# Affective_Shield.net
KiCad netlist of a schematic drawn in EAGLE
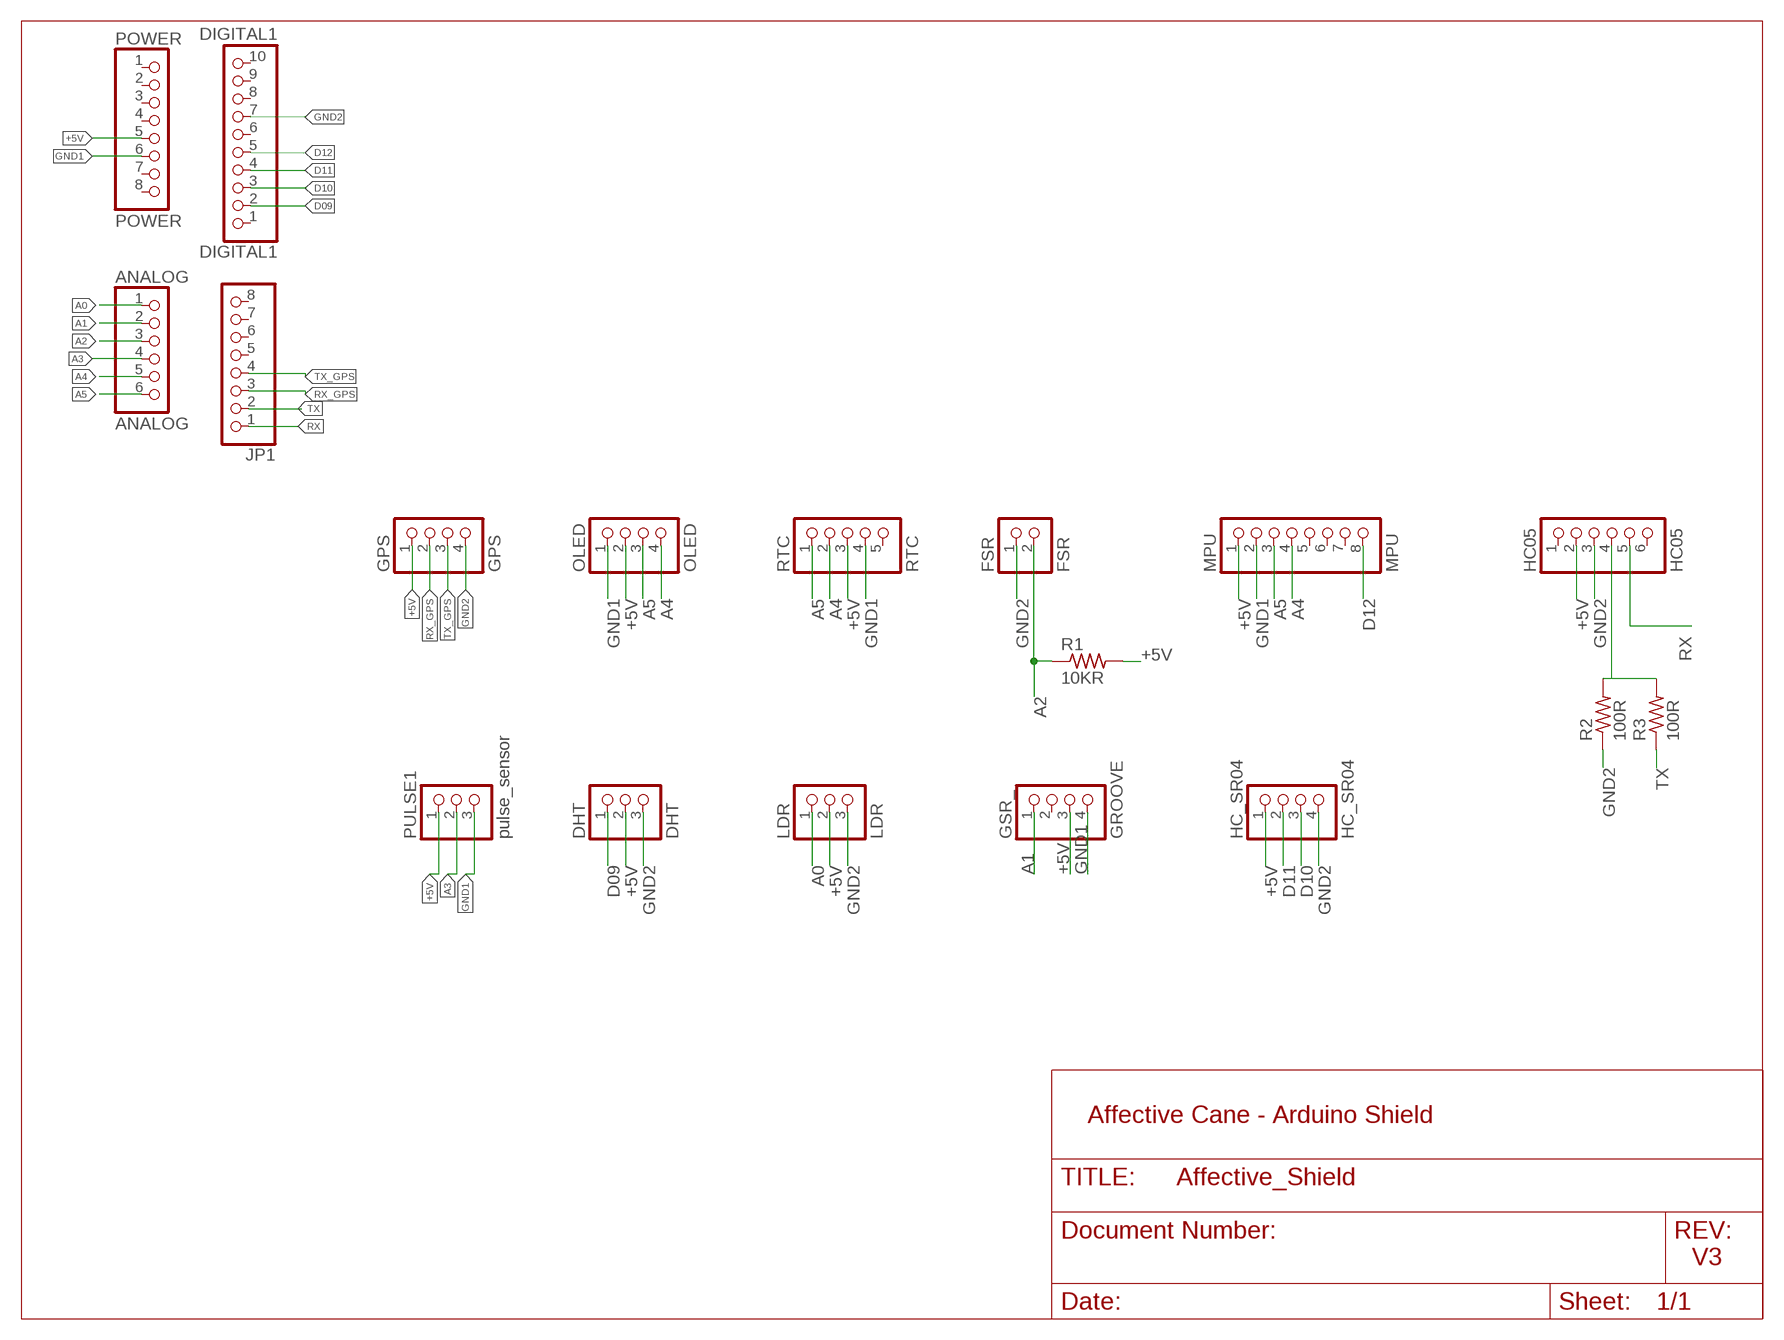
[diagram p0: schematic, sheet 1]

(export (version "E")
  (design (tool "Eeschema 10.0.6"))
  (components
    (comp (ref "ANALOG")
      (value "ANALOG")
      (footprint "eagle-import:1X06")
      (libsource (lib "eagle-import") (part "PINHD-1X6"))
    )
    (comp (ref "DHT")
      (value "DHT")
      (footprint "eagle-import:1X03")
      (libsource (lib "eagle-import") (part "PINHD-1X3"))
    )
    (comp (ref "DIGITAL1")
      (value "DIGITAL1")
      (footprint "eagle-import:1X10")
      (libsource (lib "eagle-import") (part "PINHD-1X10"))
    )
    (comp (ref "FSR")
      (value "FSR")
      (footprint "eagle-import:1X02")
      (libsource (lib "eagle-import") (part "PINHD-1X2"))
    )
    (comp (ref "GPS")
      (value "GPS")
      (footprint "eagle-import:1X04")
      (libsource (lib "eagle-import") (part "PINHD-1X4"))
    )
    (comp (ref "GSR_")
      (value "GROOVE")
      (footprint "eagle-import:1X04")
      (libsource (lib "eagle-import") (part "PINHD-1X4"))
    )
    (comp (ref "HC05")
      (value "HC05")
      (footprint "eagle-import:1X06")
      (libsource (lib "eagle-import") (part "PINHD-1X6"))
    )
    (comp (ref "HC_SR04")
      (value "HC_SR04")
      (footprint "eagle-import:1X04")
      (libsource (lib "eagle-import") (part "PINHD-1X4"))
    )
    (comp (ref "JP1")
      (value "PINHD-1X8")
      (footprint "eagle-import:1X08")
      (libsource (lib "eagle-import") (part "PINHD-1X8"))
    )
    (comp (ref "LDR")
      (value "LDR")
      (footprint "eagle-import:1X03")
      (libsource (lib "eagle-import") (part "PINHD-1X3"))
    )
    (comp (ref "MPU")
      (value "MPU")
      (footprint "eagle-import:1X08")
      (libsource (lib "eagle-import") (part "PINHD-1X8"))
    )
    (comp (ref "OLED")
      (value "OLED")
      (footprint "eagle-import:1X04")
      (libsource (lib "eagle-import") (part "PINHD-1X4"))
    )
    (comp (ref "POWER")
      (value "POWER")
      (footprint "eagle-import:1X08")
      (libsource (lib "eagle-import") (part "PINHD-1X8"))
    )
    (comp (ref "PULSE1")
      (value "pulse_sensor")
      (footprint "eagle-import:1X03")
      (libsource (lib "eagle-import") (part "PINHD-1X3"))
    )
    (comp (ref "R1")
      (value "10KR")
      (footprint "eagle-import:0204_7")
      (libsource (lib "eagle-import") (part "R-US_0204/7"))
    )
    (comp (ref "R2")
      (value "100R")
      (footprint "eagle-import:0204_7")
      (libsource (lib "eagle-import") (part "R-US_0204/7"))
    )
    (comp (ref "R3")
      (value "100R")
      (footprint "eagle-import:0204_7")
      (libsource (lib "eagle-import") (part "R-US_0204/7"))
    )
    (comp (ref "RTC")
      (value "RTC")
      (footprint "eagle-import:1X05")
      (libsource (lib "eagle-import") (part "PINHD-1X5"))
    )
  )
  (nets
    (net (code "1") (name "+5V") (class "Default")
      (node (ref "DHT") (pin "2") (pinfunction "2_2") (pintype "passive"))
      (node (ref "GPS") (pin "1") (pinfunction "1_1") (pintype "passive"))
      (node (ref "GSR_") (pin "3") (pinfunction "3_3") (pintype "passive"))
      (node (ref "HC05") (pin "2") (pinfunction "2_2") (pintype "passive"))
      (node (ref "HC_SR04") (pin "1") (pinfunction "1_1") (pintype "passive"))
      (node (ref "LDR") (pin "2") (pinfunction "2_2") (pintype "passive"))
      (node (ref "MPU") (pin "1") (pinfunction "1_1") (pintype "passive"))
      (node (ref "OLED") (pin "2") (pinfunction "2_2") (pintype "passive"))
      (node (ref "POWER") (pin "5") (pinfunction "5_5") (pintype "passive"))
      (node (ref "PULSE1") (pin "1") (pinfunction "1_1") (pintype "passive"))
      (node (ref "R1") (pin "2") (pinfunction "2_2") (pintype "passive"))
      (node (ref "RTC") (pin "3") (pinfunction "3_3") (pintype "passive"))
    )
    (net (code "2") (name "A0") (class "Default")
      (node (ref "ANALOG") (pin "1") (pinfunction "1_1") (pintype "passive"))
      (node (ref "LDR") (pin "1") (pinfunction "1_1") (pintype "passive"))
    )
    (net (code "3") (name "A1") (class "Default")
      (node (ref "ANALOG") (pin "2") (pinfunction "2_2") (pintype "passive"))
      (node (ref "GSR_") (pin "1") (pinfunction "1_1") (pintype "passive"))
    )
    (net (code "4") (name "A2") (class "Default")
      (node (ref "ANALOG") (pin "3") (pinfunction "3_3") (pintype "passive"))
      (node (ref "FSR") (pin "2") (pinfunction "2_2") (pintype "passive"))
      (node (ref "R1") (pin "1") (pinfunction "1_1") (pintype "passive"))
    )
    (net (code "5") (name "A3") (class "Default")
      (node (ref "ANALOG") (pin "4") (pinfunction "4_4") (pintype "passive"))
      (node (ref "PULSE1") (pin "2") (pinfunction "2_2") (pintype "passive"))
    )
    (net (code "6") (name "A4") (class "Default")
      (node (ref "ANALOG") (pin "5") (pinfunction "5_5") (pintype "passive"))
      (node (ref "MPU") (pin "4") (pinfunction "4_4") (pintype "passive"))
      (node (ref "OLED") (pin "4") (pinfunction "4_4") (pintype "passive"))
      (node (ref "RTC") (pin "2") (pinfunction "2_2") (pintype "passive"))
    )
    (net (code "7") (name "A5") (class "Default")
      (node (ref "ANALOG") (pin "6") (pinfunction "6_6") (pintype "passive"))
      (node (ref "MPU") (pin "3") (pinfunction "3_3") (pintype "passive"))
      (node (ref "OLED") (pin "3") (pinfunction "3_3") (pintype "passive"))
      (node (ref "RTC") (pin "1") (pinfunction "1_1") (pintype "passive"))
    )
    (net (code "8") (name "D09") (class "Default")
      (node (ref "DHT") (pin "1") (pinfunction "1_1") (pintype "passive"))
      (node (ref "DIGITAL1") (pin "2") (pinfunction "2_2") (pintype "passive"))
    )
    (net (code "9") (name "D10") (class "Default")
      (node (ref "DIGITAL1") (pin "3") (pinfunction "3_3") (pintype "passive"))
      (node (ref "HC_SR04") (pin "3") (pinfunction "3_3") (pintype "passive"))
    )
    (net (code "10") (name "D11") (class "Default")
      (node (ref "DIGITAL1") (pin "4") (pinfunction "4_4") (pintype "passive"))
      (node (ref "HC_SR04") (pin "2") (pinfunction "2_2") (pintype "passive"))
    )
    (net (code "11") (name "D12") (class "Default")
      (node (ref "DIGITAL1") (pin "5") (pinfunction "5_5") (pintype "passive"))
      (node (ref "MPU") (pin "8") (pinfunction "8_8") (pintype "passive"))
    )
    (net (code "12") (name "GND1") (class "Default")
      (node (ref "GSR_") (pin "4") (pinfunction "4_4") (pintype "passive"))
      (node (ref "MPU") (pin "2") (pinfunction "2_2") (pintype "passive"))
      (node (ref "OLED") (pin "1") (pinfunction "1_1") (pintype "passive"))
      (node (ref "POWER") (pin "6") (pinfunction "6_6") (pintype "passive"))
      (node (ref "PULSE1") (pin "3") (pinfunction "3_3") (pintype "passive"))
      (node (ref "RTC") (pin "4") (pinfunction "4_4") (pintype "passive"))
    )
    (net (code "13") (name "GND2") (class "Default")
      (node (ref "DHT") (pin "3") (pinfunction "3_3") (pintype "passive"))
      (node (ref "DIGITAL1") (pin "7") (pinfunction "7_7") (pintype "passive"))
      (node (ref "FSR") (pin "1") (pinfunction "1_1") (pintype "passive"))
      (node (ref "GPS") (pin "4") (pinfunction "4_4") (pintype "passive"))
      (node (ref "HC05") (pin "3") (pinfunction "3_3") (pintype "passive"))
      (node (ref "HC_SR04") (pin "4") (pinfunction "4_4") (pintype "passive"))
      (node (ref "LDR") (pin "3") (pinfunction "3_3") (pintype "passive"))
      (node (ref "R2") (pin "1") (pinfunction "1_1") (pintype "passive"))
    )
    (net (code "14") (name "Net-(HC05-Pad4)") (class "Default")
      (node (ref "HC05") (pin "4") (pinfunction "4_4") (pintype "passive"))
      (node (ref "R2") (pin "2") (pinfunction "2_2") (pintype "passive"))
      (node (ref "R3") (pin "2") (pinfunction "2_2") (pintype "passive"))
    )
    (net (code "15") (name "RX") (class "Default")
      (node (ref "HC05") (pin "5") (pinfunction "5_5") (pintype "passive"))
      (node (ref "JP1") (pin "1") (pinfunction "1_1") (pintype "passive"))
    )
    (net (code "16") (name "RX_GPS") (class "Default")
      (node (ref "GPS") (pin "2") (pinfunction "2_2") (pintype "passive"))
      (node (ref "JP1") (pin "3") (pinfunction "3_3") (pintype "passive"))
    )
    (net (code "17") (name "TX") (class "Default")
      (node (ref "JP1") (pin "2") (pinfunction "2_2") (pintype "passive"))
      (node (ref "R3") (pin "1") (pinfunction "1_1") (pintype "passive"))
    )
    (net (code "18") (name "TX_GPS") (class "Default")
      (node (ref "GPS") (pin "3") (pinfunction "3_3") (pintype "passive"))
      (node (ref "JP1") (pin "4") (pinfunction "4_4") (pintype "passive"))
    )
    (net (code "19") (name "unconnected-(DIGITAL1-Pad1)") (class "Default")
      (node (ref "DIGITAL1") (pin "1") (pinfunction "1_1") (pintype "passive"))
    )
    (net (code "20") (name "unconnected-(DIGITAL1-Pad6)") (class "Default")
      (node (ref "DIGITAL1") (pin "6") (pinfunction "6_6") (pintype "passive"))
    )
    (net (code "21") (name "unconnected-(DIGITAL1-Pad8)") (class "Default")
      (node (ref "DIGITAL1") (pin "8") (pinfunction "8_8") (pintype "passive"))
    )
    (net (code "22") (name "unconnected-(DIGITAL1-Pad9)") (class "Default")
      (node (ref "DIGITAL1") (pin "9") (pinfunction "9_9") (pintype "passive"))
    )
    (net (code "23") (name "unconnected-(DIGITAL1-Pad10)") (class "Default")
      (node (ref "DIGITAL1") (pin "10") (pinfunction "10_10") (pintype "passive"))
    )
    (net (code "24") (name "unconnected-(GSR_-Pad2)") (class "Default")
      (node (ref "GSR_") (pin "2") (pinfunction "2_2") (pintype "passive"))
    )
    (net (code "25") (name "unconnected-(HC05-Pad1)") (class "Default")
      (node (ref "HC05") (pin "1") (pinfunction "1_1") (pintype "passive"))
    )
    (net (code "26") (name "unconnected-(HC05-Pad6)") (class "Default")
      (node (ref "HC05") (pin "6") (pinfunction "6_6") (pintype "passive"))
    )
    (net (code "27") (name "unconnected-(JP1-Pad5)") (class "Default")
      (node (ref "JP1") (pin "5") (pinfunction "5_5") (pintype "passive"))
    )
    (net (code "28") (name "unconnected-(JP1-Pad6)") (class "Default")
      (node (ref "JP1") (pin "6") (pinfunction "6_6") (pintype "passive"))
    )
    (net (code "29") (name "unconnected-(JP1-Pad7)") (class "Default")
      (node (ref "JP1") (pin "7") (pinfunction "7_7") (pintype "passive"))
    )
    (net (code "30") (name "unconnected-(JP1-Pad8)") (class "Default")
      (node (ref "JP1") (pin "8") (pinfunction "8_8") (pintype "passive"))
    )
    (net (code "31") (name "unconnected-(MPU-Pad5)") (class "Default")
      (node (ref "MPU") (pin "5") (pinfunction "5_5") (pintype "passive"))
    )
    (net (code "32") (name "unconnected-(MPU-Pad6)") (class "Default")
      (node (ref "MPU") (pin "6") (pinfunction "6_6") (pintype "passive"))
    )
    (net (code "33") (name "unconnected-(MPU-Pad7)") (class "Default")
      (node (ref "MPU") (pin "7") (pinfunction "7_7") (pintype "passive"))
    )
    (net (code "34") (name "unconnected-(POWER-Pad1)") (class "Default")
      (node (ref "POWER") (pin "1") (pinfunction "1_1") (pintype "passive"))
    )
    (net (code "35") (name "unconnected-(POWER-Pad2)") (class "Default")
      (node (ref "POWER") (pin "2") (pinfunction "2_2") (pintype "passive"))
    )
    (net (code "36") (name "unconnected-(POWER-Pad3)") (class "Default")
      (node (ref "POWER") (pin "3") (pinfunction "3_3") (pintype "passive"))
    )
    (net (code "37") (name "unconnected-(POWER-Pad4)") (class "Default")
      (node (ref "POWER") (pin "4") (pinfunction "4_4") (pintype "passive"))
    )
    (net (code "38") (name "unconnected-(POWER-Pad7)") (class "Default")
      (node (ref "POWER") (pin "7") (pinfunction "7_7") (pintype "passive"))
    )
    (net (code "39") (name "unconnected-(POWER-Pad8)") (class "Default")
      (node (ref "POWER") (pin "8") (pinfunction "8_8") (pintype "passive"))
    )
    (net (code "40") (name "unconnected-(RTC-Pad5)") (class "Default")
      (node (ref "RTC") (pin "5") (pinfunction "5_5") (pintype "passive"))
    )
  )
)
